# RH028_1.net
KiCad netlist of a schematic drawn in EAGLE
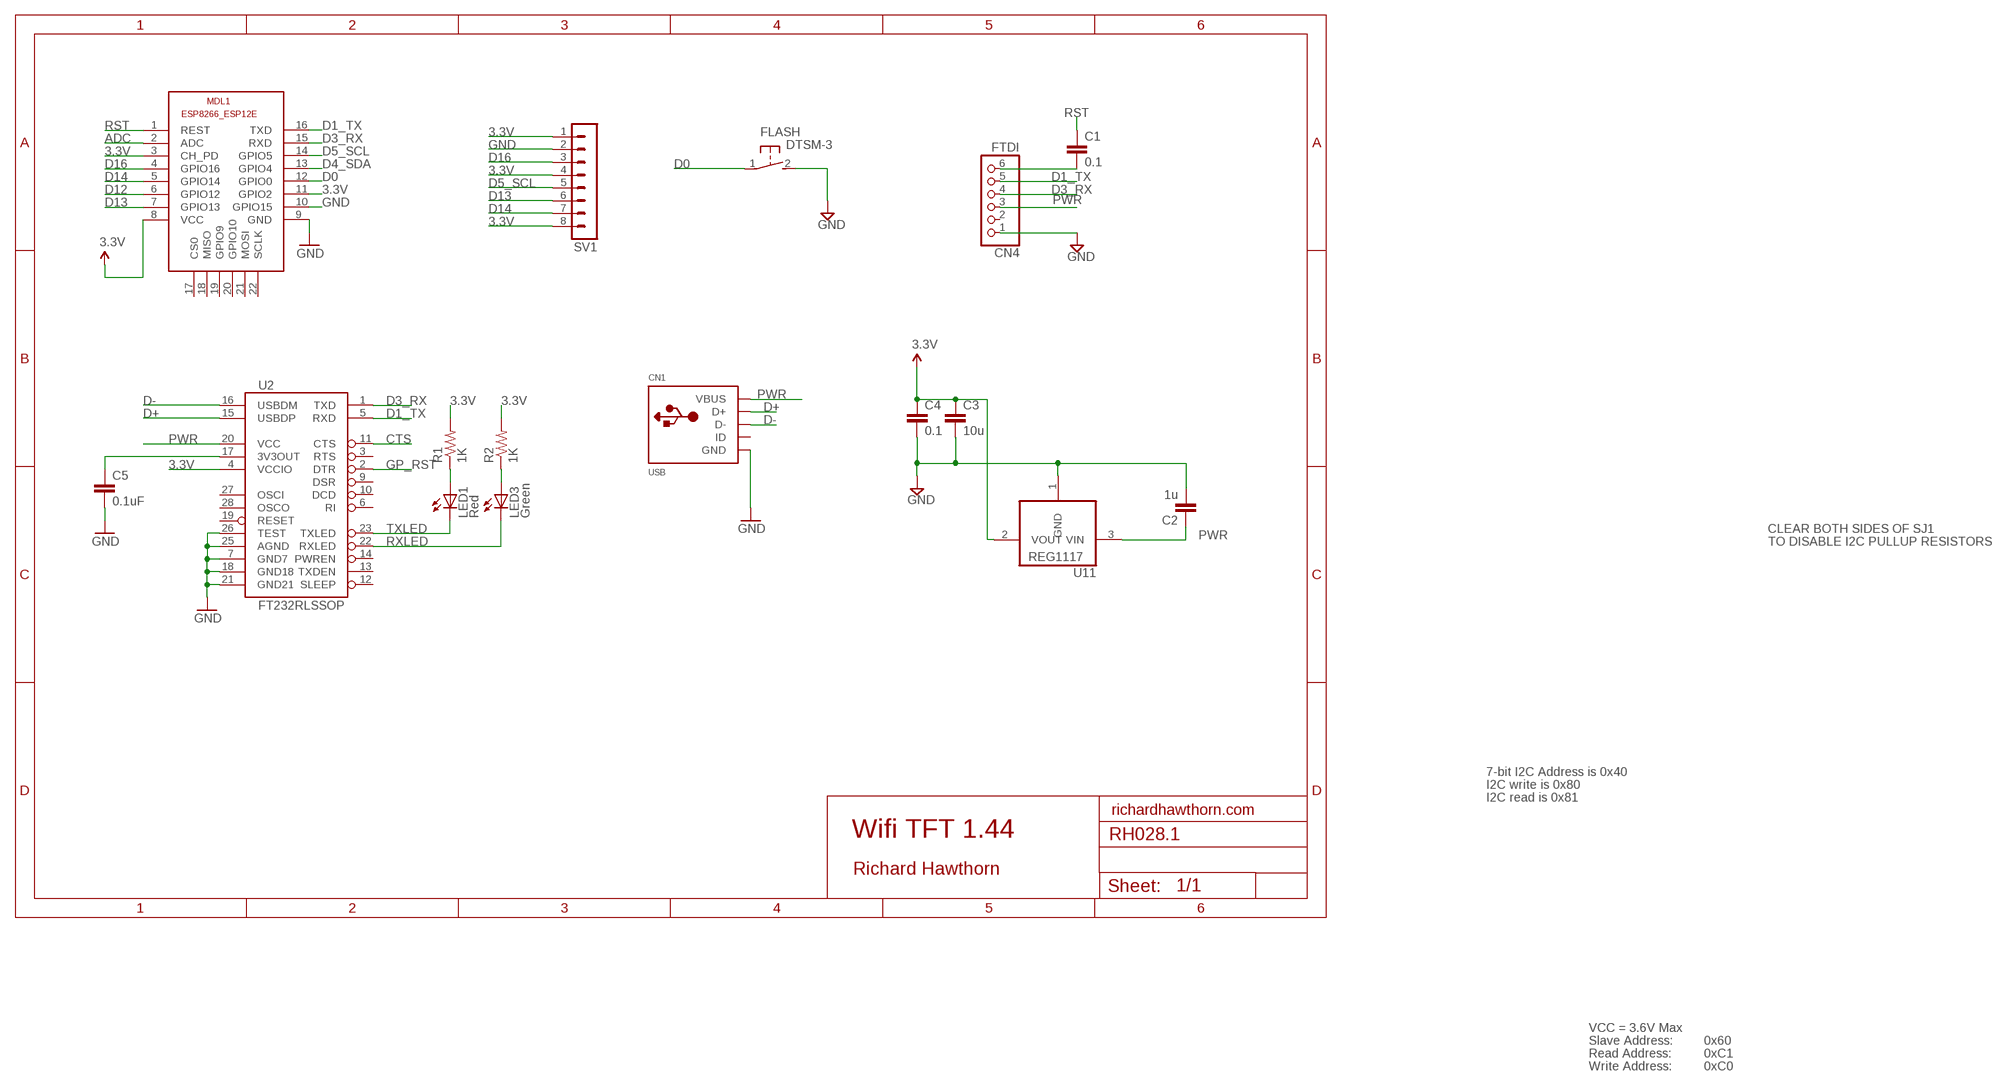
[diagram p0: schematic, sheet 1]

(export (version "E")
  (design (tool "Eeschema 10.0.6"))
  (components
    (comp (ref "C1")
      (value "0.1")
      (footprint "eagle-import:0603-CAP")
      (libsource (lib "eagle-import") (part "CAP0603-CAP"))
    )
    (comp (ref "C2")
      (value "1u")
      (footprint "eagle-import:0603-CAP")
      (libsource (lib "eagle-import") (part "CAP0603-CAP"))
    )
    (comp (ref "C3")
      (value "10u")
      (footprint "eagle-import:0805-CAP")
      (libsource (lib "eagle-import") (part "CAP0805-CAP"))
    )
    (comp (ref "C4")
      (value "0.1")
      (footprint "eagle-import:0603-CAP")
      (libsource (lib "eagle-import") (part "CAP0603-CAP"))
    )
    (comp (ref "C5")
      (value "0.1uF")
      (footprint "eagle-import:0402-CAP")
      (libsource (lib "eagle-import") (part "SparkFun_CAP0402-CAP"))
    )
    (comp (ref "CN1")
      (value "USB")
      (footprint "eagle-import:USB-MINIB")
      (libsource (lib "eagle-import") (part "USBMINIB"))
    )
    (comp (ref "CN4")
      (value "FTDI")
      (footprint "eagle-import:1X06")
      (libsource (lib "eagle-import") (part "PINHD-1X6"))
    )
    (comp (ref "FLASH")
      (value "DTSM-3")
      (footprint "eagle-import:DTSM-3")
      (libsource (lib "eagle-import") (part "DTSM-3"))
    )
    (comp (ref "LED1")
      (value "Red")
      (footprint "eagle-import:LED-0603")
      (libsource (lib "eagle-import") (part "LED0603"))
    )
    (comp (ref "LED3")
      (value "Green")
      (footprint "eagle-import:LED-0603")
      (libsource (lib "eagle-import") (part "LED0603"))
    )
    (comp (ref "MDL1")
      (value "ESP8266-12EESP8266-ESP12E")
      (footprint "eagle-import:ESP8266-ESP12E")
      (libsource (lib "eagle-import") (part "ESP8266-12EESP8266-ESP12E"))
    )
    (comp (ref "R1")
      (value "1K")
      (footprint "eagle-import:0402-RES")
      (libsource (lib "eagle-import") (part "RESISTOR0402-RES"))
    )
    (comp (ref "R2")
      (value "1K")
      (footprint "eagle-import:0402-RES")
      (libsource (lib "eagle-import") (part "RESISTOR0402-RES"))
    )
    (comp (ref "SV1")
      (value "MA08-1")
      (footprint "eagle-import:MA08-1")
      (libsource (lib "eagle-import") (part "MA08-1"))
    )
    (comp (ref "U2")
      (value "FT232RLSSOP")
      (footprint "eagle-import:SSOP28DB")
      (libsource (lib "eagle-import") (part "FT232RLSSOP"))
    )
    (comp (ref "U11")
      (value "REG1117")
      (footprint "eagle-import:SOT223")
      (libsource (lib "eagle-import") (part "REG1117"))
    )
  )
  (nets
    (net (code "1") (name "/ADC") (class "Default")
      (node (ref "MDL1") (pin "2") (pinfunction "ADC_2") (pintype "bidirectional"))
    )
    (net (code "2") (name "/CTS") (class "Default")
      (node (ref "U2") (pin "11") (pinfunction "CTS_11") (pintype "input"))
    )
    (net (code "3") (name "/D+") (class "Default")
      (node (ref "CN1") (pin "D+") (pinfunction "D+_D+") (pintype "bidirectional"))
      (node (ref "U2") (pin "15") (pinfunction "USBDP_15") (pintype "bidirectional"))
    )
    (net (code "4") (name "/D-") (class "Default")
      (node (ref "CN1") (pin "D-") (pinfunction "D-_D-") (pintype "bidirectional"))
      (node (ref "U2") (pin "16") (pinfunction "USBDM_16") (pintype "bidirectional"))
    )
    (net (code "5") (name "/D0") (class "Default")
      (node (ref "FLASH") (pin "1") (pinfunction "1_1") (pintype "passive"))
      (node (ref "MDL1") (pin "12") (pinfunction "GPIO0_12") (pintype "bidirectional"))
    )
    (net (code "6") (name "/D1_TX") (class "Default")
      (node (ref "CN4") (pin "5") (pinfunction "5_5") (pintype "passive"))
      (node (ref "MDL1") (pin "16") (pinfunction "TXD_16") (pintype "bidirectional"))
      (node (ref "U2") (pin "5") (pinfunction "RXD_5") (pintype "input"))
    )
    (net (code "7") (name "/D3_RX") (class "Default")
      (node (ref "CN4") (pin "4") (pinfunction "4_4") (pintype "passive"))
      (node (ref "MDL1") (pin "15") (pinfunction "RXD_15") (pintype "bidirectional"))
      (node (ref "U2") (pin "1") (pinfunction "TXD_1") (pintype "output"))
    )
    (net (code "8") (name "/D4_SDA") (class "Default")
      (node (ref "MDL1") (pin "13") (pinfunction "GPIO4_13") (pintype "bidirectional"))
    )
    (net (code "9") (name "/D5_SCL") (class "Default")
      (node (ref "MDL1") (pin "14") (pinfunction "GPIO5_14") (pintype "bidirectional"))
      (node (ref "SV1") (pin "5") (pinfunction "5_5") (pintype "passive"))
    )
    (net (code "10") (name "/D12") (class "Default")
      (node (ref "MDL1") (pin "6") (pinfunction "GPIO12_6") (pintype "bidirectional"))
    )
    (net (code "11") (name "/D13") (class "Default")
      (node (ref "MDL1") (pin "7") (pinfunction "GPIO13_7") (pintype "bidirectional"))
      (node (ref "SV1") (pin "6") (pinfunction "6_6") (pintype "passive"))
    )
    (net (code "12") (name "/D14") (class "Default")
      (node (ref "MDL1") (pin "5") (pinfunction "GPIO14_5") (pintype "bidirectional"))
      (node (ref "SV1") (pin "7") (pinfunction "7_7") (pintype "passive"))
    )
    (net (code "13") (name "/D16") (class "Default")
      (node (ref "MDL1") (pin "4") (pinfunction "GPIO16_4") (pintype "bidirectional"))
      (node (ref "SV1") (pin "3") (pinfunction "3_3") (pintype "passive"))
    )
    (net (code "14") (name "/GP_RST") (class "Default")
      (node (ref "U2") (pin "2") (pinfunction "DTR_2") (pintype "output"))
    )
    (net (code "15") (name "/PWR") (class "Default")
      (node (ref "C2") (pin "1") (pinfunction "1_1") (pintype "passive"))
      (node (ref "CN1") (pin "VBUS") (pinfunction "VBUS_VBUS") (pintype "power_in"))
      (node (ref "CN4") (pin "3") (pinfunction "3_3") (pintype "passive"))
      (node (ref "U11") (pin "3") (pinfunction "VIN_3") (pintype "input"))
      (node (ref "U2") (pin "20") (pinfunction "VCC_20") (pintype "power_in"))
    )
    (net (code "16") (name "/RST") (class "Default")
      (node (ref "C1") (pin "1") (pinfunction "1_1") (pintype "passive"))
      (node (ref "MDL1") (pin "1") (pinfunction "REST_1") (pintype "bidirectional"))
    )
    (net (code "17") (name "/RXLED") (class "Default")
      (node (ref "LED3") (pin "C") (pinfunction "C_C") (pintype "passive"))
      (node (ref "U2") (pin "22") (pinfunction "RXLED_22") (pintype "input"))
    )
    (net (code "18") (name "/TXLED") (class "Default")
      (node (ref "LED1") (pin "C") (pinfunction "C_C") (pintype "passive"))
      (node (ref "U2") (pin "23") (pinfunction "TXLED_23") (pintype "input"))
    )
    (net (code "19") (name "3.3V") (class "Default")
      (node (ref "C3") (pin "1") (pinfunction "1_1") (pintype "passive"))
      (node (ref "C4") (pin "1") (pinfunction "1_1") (pintype "passive"))
      (node (ref "MDL1") (pin "11") (pinfunction "GPIO2_11") (pintype "bidirectional"))
      (node (ref "MDL1") (pin "3") (pinfunction "CH_PD_3") (pintype "bidirectional"))
      (node (ref "MDL1") (pin "8") (pinfunction "VCC_8") (pintype "bidirectional"))
      (node (ref "R1") (pin "2") (pinfunction "2_2") (pintype "passive"))
      (node (ref "R2") (pin "2") (pinfunction "2_2") (pintype "passive"))
      (node (ref "SV1") (pin "1") (pinfunction "1_1") (pintype "passive"))
      (node (ref "SV1") (pin "4") (pinfunction "4_4") (pintype "passive"))
      (node (ref "SV1") (pin "8") (pinfunction "8_8") (pintype "passive"))
      (node (ref "U11") (pin "2") (pinfunction "VOUT_2") (pintype "output"))
      (node (ref "U2") (pin "4") (pinfunction "VCCIO_4") (pintype "power_in"))
    )
    (net (code "20") (name "GND") (class "Default")
      (node (ref "C2") (pin "2") (pinfunction "2_2") (pintype "passive"))
      (node (ref "C3") (pin "2") (pinfunction "2_2") (pintype "passive"))
      (node (ref "C4") (pin "2") (pinfunction "2_2") (pintype "passive"))
      (node (ref "C5") (pin "2") (pinfunction "2_2") (pintype "passive"))
      (node (ref "CN1") (pin "GND") (pinfunction "GND_GND") (pintype "power_in"))
      (node (ref "CN4") (pin "1") (pinfunction "1_1") (pintype "passive"))
      (node (ref "FLASH") (pin "2") (pinfunction "2_2") (pintype "passive"))
      (node (ref "MDL1") (pin "10") (pinfunction "GPIO15_10") (pintype "bidirectional"))
      (node (ref "MDL1") (pin "9") (pinfunction "GND_9") (pintype "bidirectional"))
      (node (ref "SV1") (pin "2") (pinfunction "2_2") (pintype "passive"))
      (node (ref "U11") (pin "1") (pinfunction "GND_1") (pintype "power_in"))
      (node (ref "U2") (pin "18") (pinfunction "GND18_18") (pintype "power_in"))
      (node (ref "U2") (pin "21") (pinfunction "GND21_21") (pintype "power_in"))
      (node (ref "U2") (pin "25") (pinfunction "AGND_25") (pintype "power_in"))
      (node (ref "U2") (pin "26") (pinfunction "TEST_26") (pintype "input"))
      (node (ref "U2") (pin "7") (pinfunction "GND7_7") (pintype "power_in"))
    )
    (net (code "21") (name "Net-(C1-Pad2)") (class "Default")
      (node (ref "C1") (pin "2") (pinfunction "2_2") (pintype "passive"))
      (node (ref "CN4") (pin "6") (pinfunction "6_6") (pintype "passive"))
    )
    (net (code "22") (name "Net-(LED1-PadA)") (class "Default")
      (node (ref "LED1") (pin "A") (pinfunction "A_A") (pintype "passive"))
      (node (ref "R1") (pin "1") (pinfunction "1_1") (pintype "passive"))
    )
    (net (code "23") (name "Net-(LED3-PadA)") (class "Default")
      (node (ref "LED3") (pin "A") (pinfunction "A_A") (pintype "passive"))
      (node (ref "R2") (pin "1") (pinfunction "1_1") (pintype "passive"))
    )
    (net (code "24") (name "Net-(U2-3V3OUT)") (class "Default")
      (node (ref "C5") (pin "1") (pinfunction "1_1") (pintype "passive"))
      (node (ref "U2") (pin "17") (pinfunction "3V3OUT_17") (pintype "output"))
    )
    (net (code "25") (name "unconnected-(CN1-PadID)") (class "Default")
      (node (ref "CN1") (pin "ID") (pinfunction "ID_ID") (pintype "bidirectional"))
    )
    (net (code "26") (name "unconnected-(CN4-Pad2)") (class "Default")
      (node (ref "CN4") (pin "2") (pinfunction "2_2") (pintype "passive"))
    )
    (net (code "27") (name "unconnected-(MDL1-CS0-Pad17)") (class "Default")
      (node (ref "MDL1") (pin "17") (pinfunction "CS0_17") (pintype "bidirectional"))
    )
    (net (code "28") (name "unconnected-(MDL1-GPIO9-Pad19)") (class "Default")
      (node (ref "MDL1") (pin "19") (pinfunction "GPIO9_19") (pintype "bidirectional"))
    )
    (net (code "29") (name "unconnected-(MDL1-GPIO10-Pad20)") (class "Default")
      (node (ref "MDL1") (pin "20") (pinfunction "GPIO10_20") (pintype "bidirectional"))
    )
    (net (code "30") (name "unconnected-(MDL1-MISO-Pad18)") (class "Default")
      (node (ref "MDL1") (pin "18") (pinfunction "MISO_18") (pintype "bidirectional"))
    )
    (net (code "31") (name "unconnected-(MDL1-MOSI-Pad21)") (class "Default")
      (node (ref "MDL1") (pin "21") (pinfunction "MOSI_21") (pintype "bidirectional"))
    )
    (net (code "32") (name "unconnected-(MDL1-SCLK-Pad22)") (class "Default")
      (node (ref "MDL1") (pin "22") (pinfunction "SCLK_22") (pintype "bidirectional"))
    )
    (net (code "33") (name "unconnected-(U2-DCD-Pad10)") (class "Default")
      (node (ref "U2") (pin "10") (pinfunction "DCD_10") (pintype "input"))
    )
    (net (code "34") (name "unconnected-(U2-DSR-Pad9)") (class "Default")
      (node (ref "U2") (pin "9") (pinfunction "DSR_9") (pintype "input"))
    )
    (net (code "35") (name "unconnected-(U2-OSCI-Pad27)") (class "Default")
      (node (ref "U2") (pin "27") (pinfunction "OSCI_27") (pintype "input"))
    )
    (net (code "36") (name "unconnected-(U2-OSCO-Pad28)") (class "Default")
      (node (ref "U2") (pin "28") (pinfunction "OSCO_28") (pintype "output"))
    )
    (net (code "37") (name "unconnected-(U2-PWREN-Pad14)") (class "Default")
      (node (ref "U2") (pin "14") (pinfunction "PWREN_14") (pintype "input"))
    )
    (net (code "38") (name "unconnected-(U2-RESET-Pad19)") (class "Default")
      (node (ref "U2") (pin "19") (pinfunction "RESET_19") (pintype "input"))
    )
    (net (code "39") (name "unconnected-(U2-RI-Pad6)") (class "Default")
      (node (ref "U2") (pin "6") (pinfunction "RI_6") (pintype "input"))
    )
    (net (code "40") (name "unconnected-(U2-RTS-Pad3)") (class "Default")
      (node (ref "U2") (pin "3") (pinfunction "RTS_3") (pintype "output"))
    )
    (net (code "41") (name "unconnected-(U2-SLEEP-Pad12)") (class "Default")
      (node (ref "U2") (pin "12") (pinfunction "SLEEP_12") (pintype "input"))
    )
    (net (code "42") (name "unconnected-(U2-TXDEN-Pad13)") (class "Default")
      (node (ref "U2") (pin "13") (pinfunction "TXDEN_13") (pintype "input"))
    )
  )
)
